# LPCB223_-_CHARGER_IF.net
KiCad netlist of a schematic drawn in Altium Designer
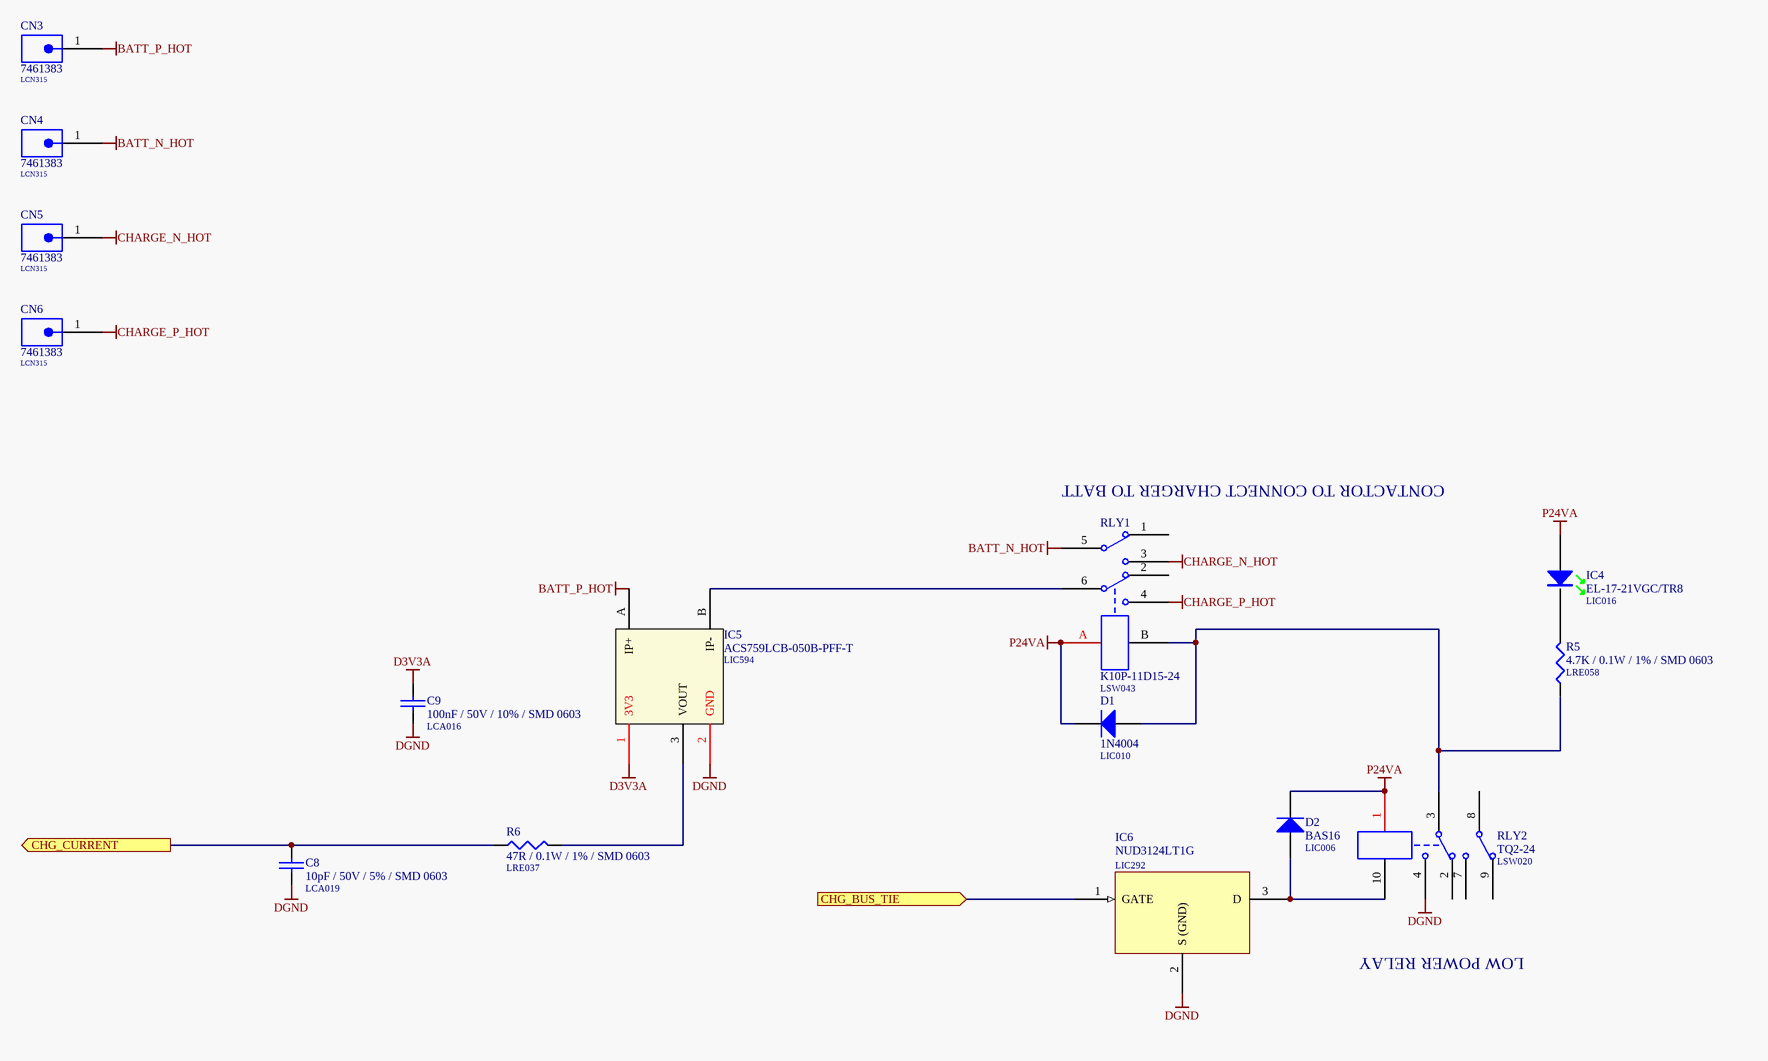
[diagram p0: LPCB223 - CHARGER IF.SchDoc]

(export (version "E")
  (design (tool "Eeschema 10.0.6"))
  (components
    (comp (ref "C8")
      (value "10pF / 50V / 5% / SMD 0603")
      (footprint "LFP011__CC1608-0603-IPC7351_B")
      (description "Capacitor, Ceramic Chip, 10pF, 50V, 5%, SMD 0603 [LCA019]")
      (fields (field (name "LDL_NUMBER") "LCA019"))
      (libsource (lib "LDL_Capacitors") (part "10pF / 50V / 5% / SMD 0603"))
    )
    (comp (ref "C9")
      (value "100nF / 50V / 10% / SMD 0603")
      (footprint "LFP011__CC1608-0603-IPC7351_B")
      (description "Capacitor, Ceramic Chip, 100nF (0.1uF), 50V, 5%, SMD 0603 [LCA016]")
      (fields (field (name "LDL_NUMBER") "LCA016"))
      (libsource (lib "LDL_Capacitors") (part "100nF / 50V / 10% / SMD 0603"))
    )
    (comp (ref "CN3")
      (value "7461383")
      (footprint "7461383")
      (description "Terminal, Bush with M5 Shank")
      (fields (field (name "LDL_NUMBER") "LCN315"))
      (libsource (lib "LDL_Connectors") (part "7461383"))
    )
    (comp (ref "CN4")
      (value "7461383")
      (footprint "7461383")
      (description "Terminal, Bush with M5 Shank")
      (fields (field (name "LDL_NUMBER") "LCN315"))
      (libsource (lib "LDL_Connectors") (part "7461383"))
    )
    (comp (ref "CN5")
      (value "7461383")
      (footprint "7461383")
      (description "Terminal, Bush with M5 Shank")
      (fields (field (name "LDL_NUMBER") "LCN315"))
      (libsource (lib "LDL_Connectors") (part "7461383"))
    )
    (comp (ref "CN6")
      (value "7461383")
      (footprint "7461383")
      (description "Terminal, Bush with M5 Shank")
      (fields (field (name "LDL_NUMBER") "LCN315"))
      (libsource (lib "LDL_Connectors") (part "7461383"))
    )
    (comp (ref "D1")
      (value "1N4004")
      (footprint "DO-41")
      (description "Diode, General Purpose Rectifier, 1A, PTH [LIC010]")
      (fields (field (name "LDL_NUMBER") "LIC010"))
      (libsource (lib "LDL_Semiconductors") (part "1N4004"))
    )
    (comp (ref "D2")
      (value "BAS16")
      (footprint "LFP021__SOT23")
      (description "Diode, Small Signal, 0.2A, 85V, SMD SOT-23 [LIC006]")
      (fields (field (name "LDL_NUMBER") "LIC006"))
      (libsource (lib "LDL_Semiconductors") (part "BAS16"))
    )
    (comp (ref "IC4")
      (value "EL-17-21VGC/TR8")
      (footprint "CR2012-0805-LED")
      (description "LED, SMD, 0805 Green [LIC016]")
      (fields (field (name "LDL_NUMBER") "LIC016"))
      (libsource (lib "LDL_Semiconductors") (part "EL-17-21VGC/TR8"))
    )
    (comp (ref "IC5")
      (value "ACS759LCB-050B-PFF-T")
      (footprint "CB-PFF")
      (description "IC, Hall Effect Current Sensor, PTH")
      (fields (field (name "LDL_NUMBER") "LIC594"))
      (libsource (lib "LDL_Semiconductors") (part "ACS759LCB-050B-PFF-T"))
    )
    (comp (ref "IC6")
      (value "NUD3124LT1G")
      (footprint "LFP021__SOT23")
      (description "IC, Relay Driver, 28V Industrial, SMD SOT23 [LIC292]")
      (fields (field (name "LDL_NUMBER") "LIC292"))
      (libsource (lib "LDL_Semiconductors") (part "NUD3124LT1G"))
    )
    (comp (ref "R5")
      (value "4.7K / 0.1W / 1% / SMD 0603")
      (footprint "LFP020__CR1608-0603-IPC7351_B")
      (description "Resistor, Ceramic Chip, 4K7, 0.1W, 1%, SMD 0603 [LRE058]")
      (fields (field (name "LDL_NUMBER") "LRE058"))
      (libsource (lib "LDL_Resistors") (part "4.7K / 0.1W / 1% / SMD 0603"))
    )
    (comp (ref "R6")
      (value "47R / 0.1W / 1% / SMD 0603")
      (footprint "LFP020__CR1608-0603-IPC7351_B")
      (description "Resistor, Ceramic Chip, 47R, 0.1W, 1%, SMD 0603 [LRE037]")
      (fields (field (name "LDL_NUMBER") "LRE037"))
      (libsource (lib "LDL_Resistors") (part "47R / 0.1W / 1% / SMD 0603"))
    )
    (comp (ref "RLY1")
      (value "K10P-11D15-24")
      (footprint "K10P-11D15-24")
      (description "Relay, DPDT, 24V, Socket Mount")
      (fields (field (name "LDL_NUMBER") "LSW043"))
      (libsource (lib "LDL_Switching") (part "K10P-11D15-24"))
    )
    (comp (ref "RLY2")
      (value "TQ2-24")
      (footprint "TQ2")
      (description "Relay, DPDT, Non Latching, 24VDC Coil, 1A Rating, PTH")
      (fields (field (name "LDL_NUMBER") "LSW020"))
      (libsource (lib "LDL_Switching") (part "TQ2-24"))
    )
  )
  (nets
    (net (code "1") (name "/CHG_BUS_TIE") (class "Default")
      (node (ref "IC6") (pin "1") (pinfunction "GATE_1") (pintype "input"))
    )
    (net (code "2") (name "/CHG_CURRENT") (class "Default")
      (node (ref "C8") (pin "1") (pintype "passive"))
      (node (ref "R6") (pin "1") (pintype "passive"))
    )
    (net (code "3") (name "BATT_N_HOT") (class "Default")
      (node (ref "CN4") (pin "1") (pinfunction "1_1") (pintype "passive"))
      (node (ref "RLY1") (pin "5") (pinfunction "5_5") (pintype "passive"))
    )
    (net (code "4") (name "BATT_P_HOT") (class "Default")
      (node (ref "CN3") (pin "1") (pinfunction "1_1") (pintype "passive"))
      (node (ref "IC5") (pin "A") (pinfunction "IP+_A") (pintype "passive"))
    )
    (net (code "5") (name "CHARGE_N_HOT") (class "Default")
      (node (ref "CN5") (pin "1") (pinfunction "1_1") (pintype "passive"))
      (node (ref "RLY1") (pin "3") (pinfunction "3_3") (pintype "passive"))
    )
    (net (code "6") (name "CHARGE_P_HOT") (class "Default")
      (node (ref "CN6") (pin "1") (pinfunction "1_1") (pintype "passive"))
      (node (ref "RLY1") (pin "4") (pinfunction "4_4") (pintype "passive"))
    )
    (net (code "7") (name "D3V3A") (class "Default")
      (node (ref "C9") (pin "1") (pintype "passive"))
      (node (ref "IC5") (pin "1") (pinfunction "3V3_1") (pintype "power_in"))
    )
    (net (code "8") (name "DGND") (class "Default")
      (node (ref "C8") (pin "2") (pintype "passive"))
      (node (ref "C9") (pin "2") (pintype "passive"))
      (node (ref "IC5") (pin "2") (pinfunction "GND_2") (pintype "power_in"))
      (node (ref "IC6") (pin "2") (pinfunction "S_(GND)_2") (pintype "passive"))
      (node (ref "RLY2") (pin "4") (pinfunction "4_4") (pintype "passive"))
    )
    (net (code "9") (name "Net-(D1-PadA)") (class "Default")
      (node (ref "D1") (pin "A") (pinfunction "A_A") (pintype "passive"))
      (node (ref "R5") (pin "1") (pintype "passive"))
      (node (ref "RLY1") (pin "B") (pinfunction "B_B") (pintype "passive"))
      (node (ref "RLY2") (pin "3") (pinfunction "3_3") (pintype "passive"))
    )
    (net (code "10") (name "Net-(D2-A)") (class "Default")
      (node (ref "D2") (pin "1") (pinfunction "A_1") (pintype "passive"))
      (node (ref "IC6") (pin "3") (pinfunction "D_3") (pintype "passive"))
      (node (ref "RLY2") (pin "10") (pinfunction "10_10") (pintype "passive"))
    )
    (net (code "11") (name "Net-(IC4-PadK)") (class "Default")
      (node (ref "IC4") (pin "K") (pintype "passive"))
      (node (ref "R5") (pin "2") (pintype "passive"))
    )
    (net (code "12") (name "Net-(IC5-IP-)") (class "Default")
      (node (ref "IC5") (pin "B") (pinfunction "IP-_B") (pintype "passive"))
      (node (ref "RLY1") (pin "6") (pinfunction "6_6") (pintype "passive"))
    )
    (net (code "13") (name "Net-(IC5-VOUT)") (class "Default")
      (node (ref "IC5") (pin "3") (pinfunction "VOUT_3") (pintype "passive"))
      (node (ref "R6") (pin "2") (pintype "passive"))
    )
    (net (code "14") (name "P24VA") (class "Default")
      (node (ref "D1") (pin "K") (pinfunction "K_K") (pintype "passive"))
      (node (ref "D2") (pin "3") (pinfunction "K_3") (pintype "passive"))
      (node (ref "IC4") (pin "A") (pintype "passive"))
      (node (ref "RLY1") (pin "A") (pinfunction "A_A") (pintype "passive"))
      (node (ref "RLY2") (pin "1") (pinfunction "1_1") (pintype "passive"))
    )
    (net (code "15") (name "unconnected-(RLY1-Pad1)") (class "Default")
      (node (ref "RLY1") (pin "1") (pinfunction "1_1") (pintype "passive"))
    )
    (net (code "16") (name "unconnected-(RLY1-Pad2)") (class "Default")
      (node (ref "RLY1") (pin "2") (pinfunction "2_2") (pintype "passive"))
    )
    (net (code "17") (name "unconnected-(RLY2-Pad2)") (class "Default")
      (node (ref "RLY2") (pin "2") (pinfunction "2_2") (pintype "passive"))
    )
    (net (code "18") (name "unconnected-(RLY2-Pad7)") (class "Default")
      (node (ref "RLY2") (pin "7") (pinfunction "7_7") (pintype "passive"))
    )
    (net (code "19") (name "unconnected-(RLY2-Pad8)") (class "Default")
      (node (ref "RLY2") (pin "8") (pinfunction "8_8") (pintype "passive"))
    )
    (net (code "20") (name "unconnected-(RLY2-Pad9)") (class "Default")
      (node (ref "RLY2") (pin "9") (pinfunction "9_9") (pintype "passive"))
    )
  )
)
